# RS232v19_9x.net
KiCad netlist of a schematic drawn in EAGLE
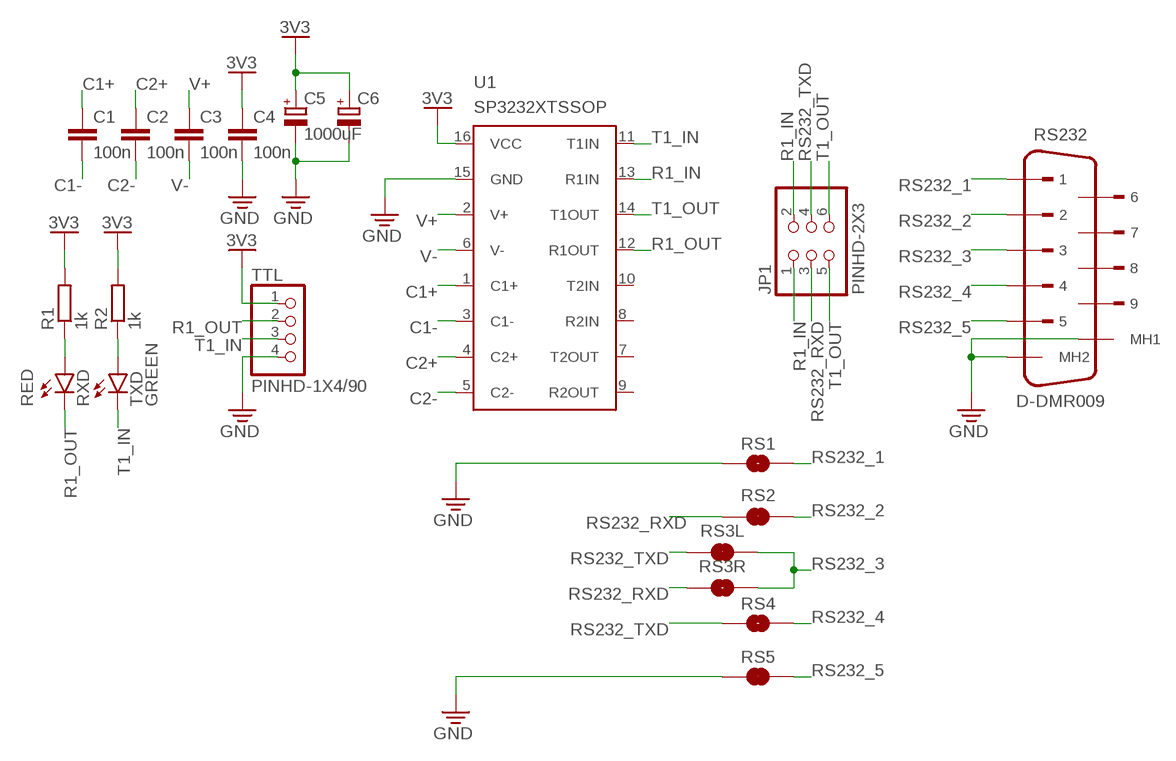
[diagram p0: schematic, sheet 1]

(export (version "E")
  (design (tool "Eeschema 10.0.6"))
  (components
    (comp (ref "C1")
      (value "100n")
      (footprint "eagle-import:C0402")
      (libsource (lib "eagle-import") (part "C-EUC0402"))
    )
    (comp (ref "C2")
      (value "100n")
      (footprint "eagle-import:C0402")
      (libsource (lib "eagle-import") (part "C-EUC0402"))
    )
    (comp (ref "C3")
      (value "100n")
      (footprint "eagle-import:C0402")
      (libsource (lib "eagle-import") (part "C-EUC0402"))
    )
    (comp (ref "C4")
      (value "100n")
      (footprint "eagle-import:C0402")
      (libsource (lib "eagle-import") (part "C-EUC0402"))
    )
    (comp (ref "C5")
      (value "1000uF")
      (footprint "eagle-import:140CLH-1010")
      (libsource (lib "eagle-import") (part "CPOL-EU140CLH-1010"))
    )
    (comp (ref "C6")
      (value "C-POL_RADIAL-11MM-DIA")
      (footprint "eagle-import:CAPPRD508W65D1000H1100B")
      (libsource (lib "eagle-import") (part "C-POLRADIAL-11MM-DIA_"))
    )
    (comp (ref "JP1")
      (value "PINHD-2X3")
      (footprint "eagle-import:2X03")
      (fields (field (name "MANUFACTURER") "Generic"))
      (libsource (lib "eagle-import") (part "PINHD-2X3"))
    )
    (comp (ref "R1")
      (value "1k")
      (footprint "eagle-import:R0402")
      (libsource (lib "eagle-import") (part "R-EU_R0402"))
    )
    (comp (ref "R2")
      (value "1k")
      (footprint "eagle-import:R0402")
      (libsource (lib "eagle-import") (part "R-EU_R0402"))
    )
    (comp (ref "RS1")
      (value "JUMPER-SMT_2_NO_SILK")
      (footprint "eagle-import:SMT-JUMPER_2_NO_SILK")
      (libsource (lib "eagle-import") (part "JUMPER-SMT_2_NO_SILK"))
    )
    (comp (ref "RS2")
      (value "JUMPER-SMT_2_NO_SILK")
      (footprint "eagle-import:SMT-JUMPER_2_NC_TRACE_SILK")
      (libsource (lib "eagle-import") (part "JUMPER-SMT_2_NC_TRACE_SILK"))
    )
    (comp (ref "RS3L")
      (value "JUMPER-SMT_2_NC_TRACE_SILK")
      (footprint "eagle-import:SMT-JUMPER_2_NC_TRACE_SILK")
      (libsource (lib "eagle-import") (part "JUMPER-SMT_2_NC_TRACE_SILK"))
    )
    (comp (ref "RS3R")
      (value "JUMPER-SMT_2_NC_TRACE_SILK")
      (footprint "eagle-import:SMT-JUMPER_2_NO_SILK")
      (libsource (lib "eagle-import") (part "JUMPER-SMT_2_NO_SILK"))
    )
    (comp (ref "RS4")
      (value "JUMPER-SMT_2_NO_SILK")
      (footprint "eagle-import:SMT-JUMPER_2_NO_SILK")
      (libsource (lib "eagle-import") (part "JUMPER-SMT_2_NO_SILK"))
    )
    (comp (ref "RS5")
      (value "JUMPER-SMT_2_NO_SILK")
      (footprint "eagle-import:SMT-JUMPER_2_NC_TRACE_SILK")
      (libsource (lib "eagle-import") (part "JUMPER-SMT_2_NC_TRACE_SILK"))
    )
    (comp (ref "RS232")
      (value "D-DMR009")
      (footprint "eagle-import:5747840-4")
      (fields (field (name "MANUFACTURER") "TE Connectivity") (field (name "MPN") "5747840-4"))
      (libsource (lib "eagle-import") (part "5747840{dblquote}"))
    )
    (comp (ref "RXD")
      (value "RED")
      (footprint "eagle-import:CHIP-LED0603")
      (libsource (lib "eagle-import") (part "LEDCHIP-LED0603"))
    )
    (comp (ref "TTL")
      (value "PINHD-1X4/90")
      (footprint "eagle-import:1X04_90")
      (fields (field (name "MANUFACTURER") "Generic"))
      (libsource (lib "eagle-import") (part "PINHD-1X4/90"))
    )
    (comp (ref "TXD")
      (value "GREEN")
      (footprint "eagle-import:CHIP-LED0603")
      (libsource (lib "eagle-import") (part "LEDCHIP-LED0603"))
    )
    (comp (ref "U1")
      (value "SP3232XTSSOP")
      (footprint "eagle-import:TSSOP16")
      (libsource (lib "eagle-import") (part "SP3232XTSSOP"))
    )
  )
  (nets
    (net (code "1") (name "/C1+") (class "Default")
      (node (ref "C1") (pin "1") (pinfunction "1_1") (pintype "passive"))
      (node (ref "U1") (pin "1") (pinfunction "C1+_1") (pintype "bidirectional"))
    )
    (net (code "2") (name "/C1-") (class "Default")
      (node (ref "C1") (pin "2") (pinfunction "2_2") (pintype "passive"))
      (node (ref "U1") (pin "3") (pinfunction "C1-_3") (pintype "bidirectional"))
    )
    (net (code "3") (name "/C2+") (class "Default")
      (node (ref "C2") (pin "1") (pinfunction "1_1") (pintype "passive"))
      (node (ref "U1") (pin "4") (pinfunction "C2+_4") (pintype "bidirectional"))
    )
    (net (code "4") (name "/C2-") (class "Default")
      (node (ref "C2") (pin "2") (pinfunction "2_2") (pintype "passive"))
      (node (ref "U1") (pin "5") (pinfunction "C2-_5") (pintype "bidirectional"))
    )
    (net (code "5") (name "/R1_IN") (class "Default")
      (node (ref "JP1") (pin "1") (pinfunction "1_1") (pintype "passive"))
      (node (ref "JP1") (pin "2") (pinfunction "2_2") (pintype "passive"))
      (node (ref "U1") (pin "13") (pinfunction "R1IN_13") (pintype "input"))
    )
    (net (code "6") (name "/R1_OUT") (class "Default")
      (node (ref "RXD") (pin "C") (pinfunction "C_C") (pintype "passive"))
      (node (ref "TTL") (pin "2") (pinfunction "2_2") (pintype "passive"))
      (node (ref "U1") (pin "12") (pinfunction "R1OUT_12") (pintype "output"))
    )
    (net (code "7") (name "/RS232_1") (class "Default")
      (node (ref "RS1") (pin "2") (pinfunction "2_2") (pintype "passive"))
      (node (ref "RS232") (pin "1") (pinfunction "1_1") (pintype "passive"))
    )
    (net (code "8") (name "/RS232_2") (class "Default")
      (node (ref "RS2") (pin "2") (pinfunction "2_2") (pintype "passive"))
      (node (ref "RS232") (pin "2") (pinfunction "2_2") (pintype "passive"))
    )
    (net (code "9") (name "/RS232_3") (class "Default")
      (node (ref "RS232") (pin "3") (pinfunction "3_3") (pintype "passive"))
      (node (ref "RS3L") (pin "2") (pinfunction "2_2") (pintype "passive"))
      (node (ref "RS3R") (pin "2") (pinfunction "2_2") (pintype "passive"))
    )
    (net (code "10") (name "/RS232_4") (class "Default")
      (node (ref "RS232") (pin "4") (pinfunction "4_4") (pintype "passive"))
      (node (ref "RS4") (pin "2") (pinfunction "2_2") (pintype "passive"))
    )
    (net (code "11") (name "/RS232_5") (class "Default")
      (node (ref "RS232") (pin "5") (pinfunction "5_5") (pintype "passive"))
      (node (ref "RS5") (pin "2") (pinfunction "2_2") (pintype "passive"))
    )
    (net (code "12") (name "/RS232_RXD") (class "Default")
      (node (ref "JP1") (pin "3") (pinfunction "3_3") (pintype "passive"))
      (node (ref "RS2") (pin "1") (pinfunction "1_1") (pintype "passive"))
      (node (ref "RS3R") (pin "1") (pinfunction "1_1") (pintype "passive"))
    )
    (net (code "13") (name "/RS232_TXD") (class "Default")
      (node (ref "JP1") (pin "4") (pinfunction "4_4") (pintype "passive"))
      (node (ref "RS3L") (pin "1") (pinfunction "1_1") (pintype "passive"))
      (node (ref "RS4") (pin "1") (pinfunction "1_1") (pintype "passive"))
    )
    (net (code "14") (name "/T1_IN") (class "Default")
      (node (ref "TTL") (pin "3") (pinfunction "3_3") (pintype "passive"))
      (node (ref "TXD") (pin "C") (pinfunction "C_C") (pintype "passive"))
      (node (ref "U1") (pin "11") (pinfunction "T1IN_11") (pintype "input"))
    )
    (net (code "15") (name "/T1_OUT") (class "Default")
      (node (ref "JP1") (pin "5") (pinfunction "5_5") (pintype "passive"))
      (node (ref "JP1") (pin "6") (pinfunction "6_6") (pintype "passive"))
      (node (ref "U1") (pin "14") (pinfunction "T1OUT_14") (pintype "output"))
    )
    (net (code "16") (name "/V+") (class "Default")
      (node (ref "C3") (pin "1") (pinfunction "1_1") (pintype "passive"))
      (node (ref "U1") (pin "2") (pinfunction "V+_2") (pintype "power_in"))
    )
    (net (code "17") (name "/V-") (class "Default")
      (node (ref "C3") (pin "2") (pinfunction "2_2") (pintype "passive"))
      (node (ref "U1") (pin "6") (pinfunction "V-_6") (pintype "power_in"))
    )
    (net (code "18") (name "3V3") (class "Default")
      (node (ref "C4") (pin "1") (pinfunction "1_1") (pintype "passive"))
      (node (ref "C5") (pin "+") (pinfunction "+_+") (pintype "passive"))
      (node (ref "C6") (pin "1") (pinfunction "+_1") (pintype "passive"))
      (node (ref "R1") (pin "2") (pinfunction "2_2") (pintype "passive"))
      (node (ref "R2") (pin "2") (pinfunction "2_2") (pintype "passive"))
      (node (ref "TTL") (pin "1") (pinfunction "1_1") (pintype "passive"))
      (node (ref "U1") (pin "16") (pinfunction "VCC_16") (pintype "power_in"))
    )
    (net (code "19") (name "GND") (class "Default")
      (node (ref "C4") (pin "2") (pinfunction "2_2") (pintype "passive"))
      (node (ref "C5") (pin "-") (pinfunction "-_-") (pintype "passive"))
      (node (ref "C6") (pin "2") (pinfunction "-_2") (pintype "passive"))
      (node (ref "RS1") (pin "1") (pinfunction "1_1") (pintype "passive"))
      (node (ref "RS232") (pin "MH1") (pinfunction "MH2_MH1") (pintype "power_in"))
      (node (ref "RS232") (pin "MH2") (pinfunction "MH1_MH2") (pintype "power_in"))
      (node (ref "RS5") (pin "1") (pinfunction "1_1") (pintype "passive"))
      (node (ref "TTL") (pin "4") (pinfunction "4_4") (pintype "passive"))
      (node (ref "U1") (pin "15") (pinfunction "GND_15") (pintype "power_in"))
    )
    (net (code "20") (name "Net-(R1-Pad1)") (class "Default")
      (node (ref "R1") (pin "1") (pinfunction "1_1") (pintype "passive"))
      (node (ref "RXD") (pin "A") (pinfunction "A_A") (pintype "passive"))
    )
    (net (code "21") (name "Net-(R2-Pad1)") (class "Default")
      (node (ref "R2") (pin "1") (pinfunction "1_1") (pintype "passive"))
      (node (ref "TXD") (pin "A") (pinfunction "A_A") (pintype "passive"))
    )
    (net (code "22") (name "unconnected-(RS232-Pad6)") (class "Default")
      (node (ref "RS232") (pin "6") (pinfunction "6_6") (pintype "passive"))
    )
    (net (code "23") (name "unconnected-(RS232-Pad7)") (class "Default")
      (node (ref "RS232") (pin "7") (pinfunction "7_7") (pintype "passive"))
    )
    (net (code "24") (name "unconnected-(RS232-Pad8)") (class "Default")
      (node (ref "RS232") (pin "8") (pinfunction "8_8") (pintype "passive"))
    )
    (net (code "25") (name "unconnected-(RS232-Pad9)") (class "Default")
      (node (ref "RS232") (pin "9") (pinfunction "9_9") (pintype "passive"))
    )
    (net (code "26") (name "unconnected-(U1-R2IN-Pad8)") (class "Default")
      (node (ref "U1") (pin "8") (pinfunction "R2IN_8") (pintype "input"))
    )
    (net (code "27") (name "unconnected-(U1-R2OUT-Pad9)") (class "Default")
      (node (ref "U1") (pin "9") (pinfunction "R2OUT_9") (pintype "output"))
    )
    (net (code "28") (name "unconnected-(U1-T2IN-Pad10)") (class "Default")
      (node (ref "U1") (pin "10") (pinfunction "T2IN_10") (pintype "input"))
    )
    (net (code "29") (name "unconnected-(U1-T2OUT-Pad7)") (class "Default")
      (node (ref "U1") (pin "7") (pinfunction "T2OUT_7") (pintype "output"))
    )
  )
)
